# hall_sensors.net
KiCad netlist of a schematic drawn in Altium Designer
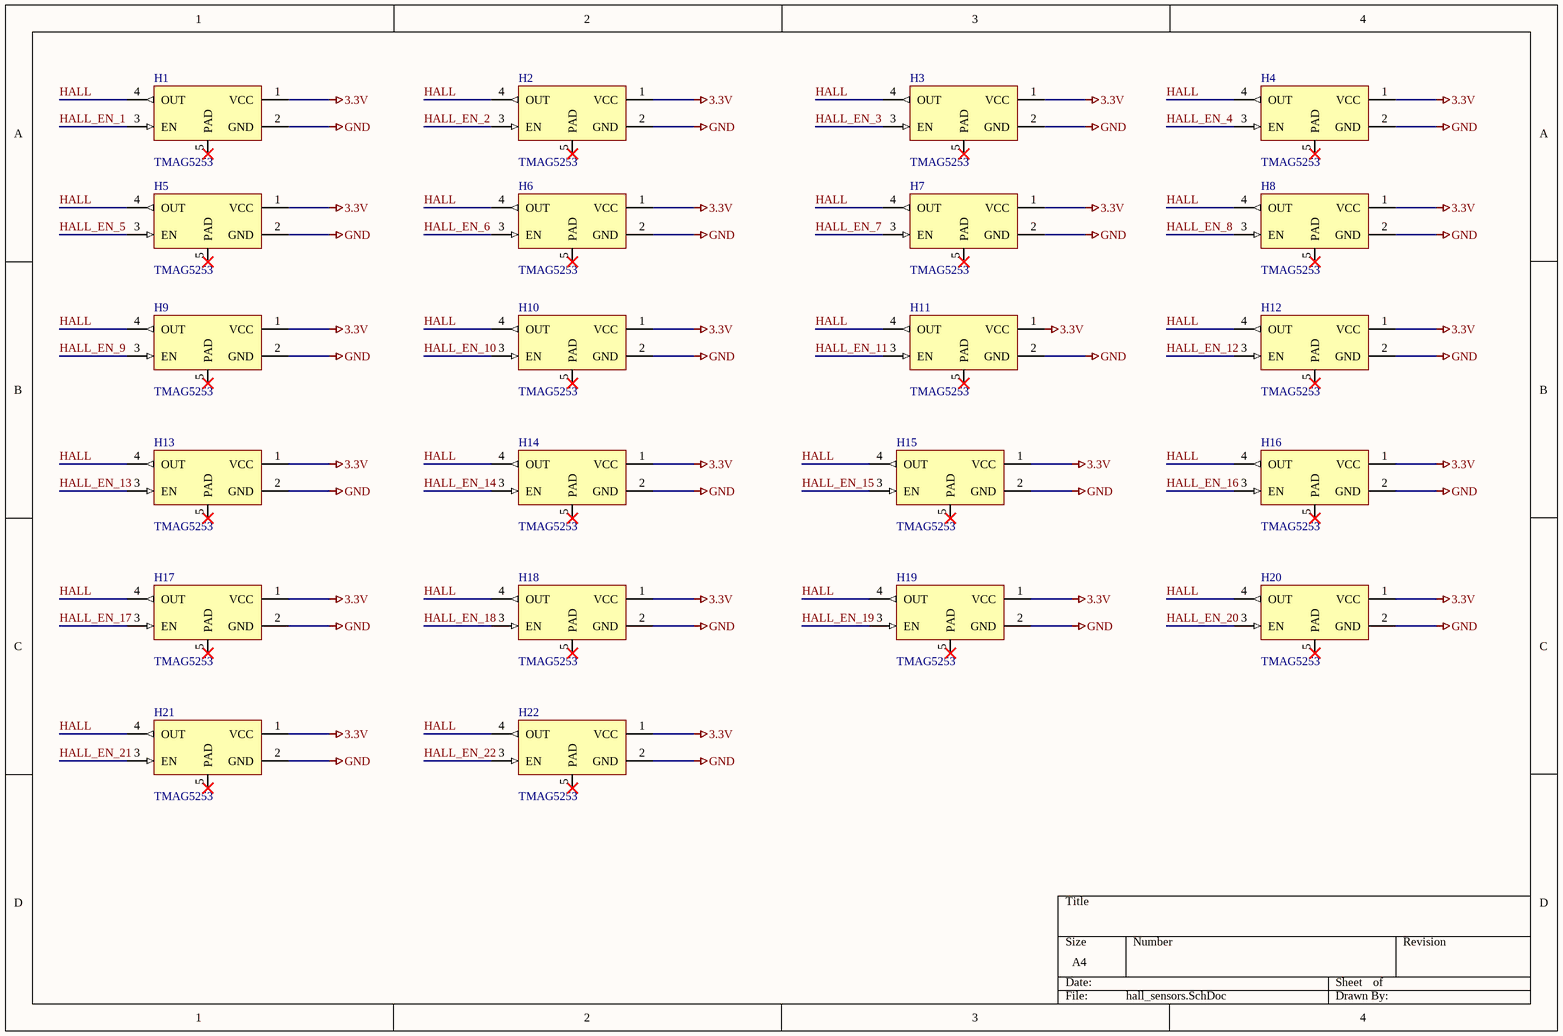
[diagram p0: hall_sensors.SchDoc]

(export (version "E")
  (design (tool "Eeschema 10.0.6"))
  (components
    (comp (ref "H1")
      (value "TMAG5253")
      (footprint "CHOCO_KEYBOARD:IC_TMAG5253BA3IQDMRR")
      (description "Low-power linear Hall-effect sensor with enable pin in ultrasmall X2SON package")
      (fields (field (name "MF") "Texas Instruments") (field (name "MP") "TMAG5253BA3IQDMRR"))
      (libsource (lib "CHOCO_KEYBOARD") (part "TMAG5253"))
    )
    (comp (ref "H2")
      (value "TMAG5253")
      (footprint "CHOCO_KEYBOARD:IC_TMAG5253BA3IQDMRR")
      (description "Low-power linear Hall-effect sensor with enable pin in ultrasmall X2SON package")
      (fields (field (name "MF") "Texas Instruments") (field (name "MP") "TMAG5253BA3IQDMRR"))
      (libsource (lib "CHOCO_KEYBOARD") (part "TMAG5253"))
    )
    (comp (ref "H3")
      (value "TMAG5253")
      (footprint "CHOCO_KEYBOARD:IC_TMAG5253BA3IQDMRR")
      (description "Low-power linear Hall-effect sensor with enable pin in ultrasmall X2SON package")
      (fields (field (name "MF") "Texas Instruments") (field (name "MP") "TMAG5253BA3IQDMRR"))
      (libsource (lib "CHOCO_KEYBOARD") (part "TMAG5253"))
    )
    (comp (ref "H4")
      (value "TMAG5253")
      (footprint "CHOCO_KEYBOARD:IC_TMAG5253BA3IQDMRR")
      (description "Low-power linear Hall-effect sensor with enable pin in ultrasmall X2SON package")
      (fields (field (name "MF") "Texas Instruments") (field (name "MP") "TMAG5253BA3IQDMRR"))
      (libsource (lib "CHOCO_KEYBOARD") (part "TMAG5253"))
    )
    (comp (ref "H5")
      (value "TMAG5253")
      (footprint "CHOCO_KEYBOARD:IC_TMAG5253BA3IQDMRR")
      (description "Low-power linear Hall-effect sensor with enable pin in ultrasmall X2SON package")
      (fields (field (name "MF") "Texas Instruments") (field (name "MP") "TMAG5253BA3IQDMRR"))
      (libsource (lib "CHOCO_KEYBOARD") (part "TMAG5253"))
    )
    (comp (ref "H6")
      (value "TMAG5253")
      (footprint "CHOCO_KEYBOARD:IC_TMAG5253BA3IQDMRR")
      (description "Low-power linear Hall-effect sensor with enable pin in ultrasmall X2SON package")
      (fields (field (name "MF") "Texas Instruments") (field (name "MP") "TMAG5253BA3IQDMRR"))
      (libsource (lib "CHOCO_KEYBOARD") (part "TMAG5253"))
    )
    (comp (ref "H7")
      (value "TMAG5253")
      (footprint "CHOCO_KEYBOARD:IC_TMAG5253BA3IQDMRR")
      (description "Low-power linear Hall-effect sensor with enable pin in ultrasmall X2SON package")
      (fields (field (name "MF") "Texas Instruments") (field (name "MP") "TMAG5253BA3IQDMRR"))
      (libsource (lib "CHOCO_KEYBOARD") (part "TMAG5253"))
    )
    (comp (ref "H8")
      (value "TMAG5253")
      (footprint "CHOCO_KEYBOARD:IC_TMAG5253BA3IQDMRR")
      (description "Low-power linear Hall-effect sensor with enable pin in ultrasmall X2SON package")
      (fields (field (name "MF") "Texas Instruments") (field (name "MP") "TMAG5253BA3IQDMRR"))
      (libsource (lib "CHOCO_KEYBOARD") (part "TMAG5253"))
    )
    (comp (ref "H9")
      (value "TMAG5253")
      (footprint "CHOCO_KEYBOARD:IC_TMAG5253BA3IQDMRR")
      (description "Low-power linear Hall-effect sensor with enable pin in ultrasmall X2SON package")
      (fields (field (name "MF") "Texas Instruments") (field (name "MP") "TMAG5253BA3IQDMRR"))
      (libsource (lib "CHOCO_KEYBOARD") (part "TMAG5253"))
    )
    (comp (ref "H10")
      (value "TMAG5253")
      (footprint "CHOCO_KEYBOARD:IC_TMAG5253BA3IQDMRR")
      (description "Low-power linear Hall-effect sensor with enable pin in ultrasmall X2SON package")
      (fields (field (name "MF") "Texas Instruments") (field (name "MP") "TMAG5253BA3IQDMRR"))
      (libsource (lib "CHOCO_KEYBOARD") (part "TMAG5253"))
    )
    (comp (ref "H11")
      (value "TMAG5253")
      (footprint "CHOCO_KEYBOARD:IC_TMAG5253BA3IQDMRR")
      (description "Low-power linear Hall-effect sensor with enable pin in ultrasmall X2SON package")
      (fields (field (name "MF") "Texas Instruments") (field (name "MP") "TMAG5253BA3IQDMRR"))
      (libsource (lib "CHOCO_KEYBOARD") (part "TMAG5253"))
    )
    (comp (ref "H12")
      (value "TMAG5253")
      (footprint "CHOCO_KEYBOARD:IC_TMAG5253BA3IQDMRR")
      (description "Low-power linear Hall-effect sensor with enable pin in ultrasmall X2SON package")
      (fields (field (name "MF") "Texas Instruments") (field (name "MP") "TMAG5253BA3IQDMRR"))
      (libsource (lib "CHOCO_KEYBOARD") (part "TMAG5253"))
    )
    (comp (ref "H13")
      (value "TMAG5253")
      (footprint "CHOCO_KEYBOARD:IC_TMAG5253BA3IQDMRR")
      (description "Low-power linear Hall-effect sensor with enable pin in ultrasmall X2SON package")
      (fields (field (name "MF") "Texas Instruments") (field (name "MP") "TMAG5253BA3IQDMRR"))
      (libsource (lib "CHOCO_KEYBOARD") (part "TMAG5253"))
    )
    (comp (ref "H14")
      (value "TMAG5253")
      (footprint "CHOCO_KEYBOARD:IC_TMAG5253BA3IQDMRR")
      (description "Low-power linear Hall-effect sensor with enable pin in ultrasmall X2SON package")
      (fields (field (name "MF") "Texas Instruments") (field (name "MP") "TMAG5253BA3IQDMRR"))
      (libsource (lib "CHOCO_KEYBOARD") (part "TMAG5253"))
    )
    (comp (ref "H15")
      (value "TMAG5253")
      (footprint "CHOCO_KEYBOARD:IC_TMAG5253BA3IQDMRR")
      (description "Low-power linear Hall-effect sensor with enable pin in ultrasmall X2SON package")
      (fields (field (name "MF") "Texas Instruments") (field (name "MP") "TMAG5253BA3IQDMRR"))
      (libsource (lib "CHOCO_KEYBOARD") (part "TMAG5253"))
    )
    (comp (ref "H16")
      (value "TMAG5253")
      (footprint "CHOCO_KEYBOARD:IC_TMAG5253BA3IQDMRR")
      (description "Low-power linear Hall-effect sensor with enable pin in ultrasmall X2SON package")
      (fields (field (name "MF") "Texas Instruments") (field (name "MP") "TMAG5253BA3IQDMRR"))
      (libsource (lib "CHOCO_KEYBOARD") (part "TMAG5253"))
    )
    (comp (ref "H17")
      (value "TMAG5253")
      (footprint "CHOCO_KEYBOARD:IC_TMAG5253BA3IQDMRR")
      (description "Low-power linear Hall-effect sensor with enable pin in ultrasmall X2SON package")
      (fields (field (name "MF") "Texas Instruments") (field (name "MP") "TMAG5253BA3IQDMRR"))
      (libsource (lib "CHOCO_KEYBOARD") (part "TMAG5253"))
    )
    (comp (ref "H18")
      (value "TMAG5253")
      (footprint "CHOCO_KEYBOARD:IC_TMAG5253BA3IQDMRR")
      (description "Low-power linear Hall-effect sensor with enable pin in ultrasmall X2SON package")
      (fields (field (name "MF") "Texas Instruments") (field (name "MP") "TMAG5253BA3IQDMRR"))
      (libsource (lib "CHOCO_KEYBOARD") (part "TMAG5253"))
    )
    (comp (ref "H19")
      (value "TMAG5253")
      (footprint "CHOCO_KEYBOARD:IC_TMAG5253BA3IQDMRR")
      (description "Low-power linear Hall-effect sensor with enable pin in ultrasmall X2SON package")
      (fields (field (name "MF") "Texas Instruments") (field (name "MP") "TMAG5253BA3IQDMRR"))
      (libsource (lib "CHOCO_KEYBOARD") (part "TMAG5253"))
    )
    (comp (ref "H20")
      (value "TMAG5253")
      (footprint "CHOCO_KEYBOARD:IC_TMAG5253BA3IQDMRR")
      (description "Low-power linear Hall-effect sensor with enable pin in ultrasmall X2SON package")
      (fields (field (name "MF") "Texas Instruments") (field (name "MP") "TMAG5253BA3IQDMRR"))
      (libsource (lib "CHOCO_KEYBOARD") (part "TMAG5253"))
    )
    (comp (ref "H21")
      (value "TMAG5253")
      (footprint "CHOCO_KEYBOARD:IC_TMAG5253BA3IQDMRR")
      (description "Low-power linear Hall-effect sensor with enable pin in ultrasmall X2SON package")
      (fields (field (name "MF") "Texas Instruments") (field (name "MP") "TMAG5253BA3IQDMRR"))
      (libsource (lib "CHOCO_KEYBOARD") (part "TMAG5253"))
    )
    (comp (ref "H22")
      (value "TMAG5253")
      (footprint "CHOCO_KEYBOARD:IC_TMAG5253BA3IQDMRR")
      (description "Low-power linear Hall-effect sensor with enable pin in ultrasmall X2SON package")
      (fields (field (name "MF") "Texas Instruments") (field (name "MP") "TMAG5253BA3IQDMRR"))
      (libsource (lib "CHOCO_KEYBOARD") (part "TMAG5253"))
    )
  )
  (nets
    (net (code "1") (name "/HALL") (class "Default")
      (node (ref "H1") (pin "4") (pinfunction "OUT_4") (pintype "output"))
      (node (ref "H10") (pin "4") (pinfunction "OUT_4") (pintype "output"))
      (node (ref "H11") (pin "4") (pinfunction "OUT_4") (pintype "output"))
      (node (ref "H12") (pin "4") (pinfunction "OUT_4") (pintype "output"))
      (node (ref "H13") (pin "4") (pinfunction "OUT_4") (pintype "output"))
      (node (ref "H14") (pin "4") (pinfunction "OUT_4") (pintype "output"))
      (node (ref "H15") (pin "4") (pinfunction "OUT_4") (pintype "output"))
      (node (ref "H16") (pin "4") (pinfunction "OUT_4") (pintype "output"))
      (node (ref "H17") (pin "4") (pinfunction "OUT_4") (pintype "output"))
      (node (ref "H18") (pin "4") (pinfunction "OUT_4") (pintype "output"))
      (node (ref "H19") (pin "4") (pinfunction "OUT_4") (pintype "output"))
      (node (ref "H2") (pin "4") (pinfunction "OUT_4") (pintype "output"))
      (node (ref "H20") (pin "4") (pinfunction "OUT_4") (pintype "output"))
      (node (ref "H21") (pin "4") (pinfunction "OUT_4") (pintype "output"))
      (node (ref "H22") (pin "4") (pinfunction "OUT_4") (pintype "output"))
      (node (ref "H3") (pin "4") (pinfunction "OUT_4") (pintype "output"))
      (node (ref "H4") (pin "4") (pinfunction "OUT_4") (pintype "output"))
      (node (ref "H5") (pin "4") (pinfunction "OUT_4") (pintype "output"))
      (node (ref "H6") (pin "4") (pinfunction "OUT_4") (pintype "output"))
      (node (ref "H7") (pin "4") (pinfunction "OUT_4") (pintype "output"))
      (node (ref "H8") (pin "4") (pinfunction "OUT_4") (pintype "output"))
      (node (ref "H9") (pin "4") (pinfunction "OUT_4") (pintype "output"))
    )
    (net (code "2") (name "/HALL_EN_1") (class "Default")
      (node (ref "H1") (pin "3") (pinfunction "EN_3") (pintype "input"))
    )
    (net (code "3") (name "/HALL_EN_2") (class "Default")
      (node (ref "H2") (pin "3") (pinfunction "EN_3") (pintype "input"))
    )
    (net (code "4") (name "/HALL_EN_3") (class "Default")
      (node (ref "H3") (pin "3") (pinfunction "EN_3") (pintype "input"))
    )
    (net (code "5") (name "/HALL_EN_4") (class "Default")
      (node (ref "H4") (pin "3") (pinfunction "EN_3") (pintype "input"))
    )
    (net (code "6") (name "/HALL_EN_5") (class "Default")
      (node (ref "H5") (pin "3") (pinfunction "EN_3") (pintype "input"))
    )
    (net (code "7") (name "/HALL_EN_6") (class "Default")
      (node (ref "H6") (pin "3") (pinfunction "EN_3") (pintype "input"))
    )
    (net (code "8") (name "/HALL_EN_7") (class "Default")
      (node (ref "H7") (pin "3") (pinfunction "EN_3") (pintype "input"))
    )
    (net (code "9") (name "/HALL_EN_8") (class "Default")
      (node (ref "H8") (pin "3") (pinfunction "EN_3") (pintype "input"))
    )
    (net (code "10") (name "/HALL_EN_9") (class "Default")
      (node (ref "H9") (pin "3") (pinfunction "EN_3") (pintype "input"))
    )
    (net (code "11") (name "/HALL_EN_10") (class "Default")
      (node (ref "H10") (pin "3") (pinfunction "EN_3") (pintype "input"))
    )
    (net (code "12") (name "/HALL_EN_11") (class "Default")
      (node (ref "H11") (pin "3") (pinfunction "EN_3") (pintype "input"))
    )
    (net (code "13") (name "/HALL_EN_12") (class "Default")
      (node (ref "H12") (pin "3") (pinfunction "EN_3") (pintype "input"))
    )
    (net (code "14") (name "/HALL_EN_13") (class "Default")
      (node (ref "H13") (pin "3") (pinfunction "EN_3") (pintype "input"))
    )
    (net (code "15") (name "/HALL_EN_14") (class "Default")
      (node (ref "H14") (pin "3") (pinfunction "EN_3") (pintype "input"))
    )
    (net (code "16") (name "/HALL_EN_15") (class "Default")
      (node (ref "H15") (pin "3") (pinfunction "EN_3") (pintype "input"))
    )
    (net (code "17") (name "/HALL_EN_16") (class "Default")
      (node (ref "H16") (pin "3") (pinfunction "EN_3") (pintype "input"))
    )
    (net (code "18") (name "/HALL_EN_17") (class "Default")
      (node (ref "H17") (pin "3") (pinfunction "EN_3") (pintype "input"))
    )
    (net (code "19") (name "/HALL_EN_18") (class "Default")
      (node (ref "H18") (pin "3") (pinfunction "EN_3") (pintype "input"))
    )
    (net (code "20") (name "/HALL_EN_19") (class "Default")
      (node (ref "H19") (pin "3") (pinfunction "EN_3") (pintype "input"))
    )
    (net (code "21") (name "/HALL_EN_20") (class "Default")
      (node (ref "H20") (pin "3") (pinfunction "EN_3") (pintype "input"))
    )
    (net (code "22") (name "/HALL_EN_21") (class "Default")
      (node (ref "H21") (pin "3") (pinfunction "EN_3") (pintype "input"))
    )
    (net (code "23") (name "/HALL_EN_22") (class "Default")
      (node (ref "H22") (pin "3") (pinfunction "EN_3") (pintype "input"))
    )
    (net (code "24") (name "3.3V") (class "Default")
      (node (ref "H1") (pin "1") (pinfunction "VCC_1") (pintype "power_in"))
      (node (ref "H10") (pin "1") (pinfunction "VCC_1") (pintype "power_in"))
      (node (ref "H11") (pin "1") (pinfunction "VCC_1") (pintype "power_in"))
      (node (ref "H12") (pin "1") (pinfunction "VCC_1") (pintype "power_in"))
      (node (ref "H13") (pin "1") (pinfunction "VCC_1") (pintype "power_in"))
      (node (ref "H14") (pin "1") (pinfunction "VCC_1") (pintype "power_in"))
      (node (ref "H15") (pin "1") (pinfunction "VCC_1") (pintype "power_in"))
      (node (ref "H16") (pin "1") (pinfunction "VCC_1") (pintype "power_in"))
      (node (ref "H17") (pin "1") (pinfunction "VCC_1") (pintype "power_in"))
      (node (ref "H18") (pin "1") (pinfunction "VCC_1") (pintype "power_in"))
      (node (ref "H19") (pin "1") (pinfunction "VCC_1") (pintype "power_in"))
      (node (ref "H2") (pin "1") (pinfunction "VCC_1") (pintype "power_in"))
      (node (ref "H20") (pin "1") (pinfunction "VCC_1") (pintype "power_in"))
      (node (ref "H21") (pin "1") (pinfunction "VCC_1") (pintype "power_in"))
      (node (ref "H22") (pin "1") (pinfunction "VCC_1") (pintype "power_in"))
      (node (ref "H3") (pin "1") (pinfunction "VCC_1") (pintype "power_in"))
      (node (ref "H4") (pin "1") (pinfunction "VCC_1") (pintype "power_in"))
      (node (ref "H5") (pin "1") (pinfunction "VCC_1") (pintype "power_in"))
      (node (ref "H6") (pin "1") (pinfunction "VCC_1") (pintype "power_in"))
      (node (ref "H7") (pin "1") (pinfunction "VCC_1") (pintype "power_in"))
      (node (ref "H8") (pin "1") (pinfunction "VCC_1") (pintype "power_in"))
      (node (ref "H9") (pin "1") (pinfunction "VCC_1") (pintype "power_in"))
    )
    (net (code "25") (name "GND") (class "Default")
      (node (ref "H1") (pin "2") (pinfunction "GND_2") (pintype "power_in"))
      (node (ref "H10") (pin "2") (pinfunction "GND_2") (pintype "power_in"))
      (node (ref "H11") (pin "2") (pinfunction "GND_2") (pintype "power_in"))
      (node (ref "H12") (pin "2") (pinfunction "GND_2") (pintype "power_in"))
      (node (ref "H13") (pin "2") (pinfunction "GND_2") (pintype "power_in"))
      (node (ref "H14") (pin "2") (pinfunction "GND_2") (pintype "power_in"))
      (node (ref "H15") (pin "2") (pinfunction "GND_2") (pintype "power_in"))
      (node (ref "H16") (pin "2") (pinfunction "GND_2") (pintype "power_in"))
      (node (ref "H17") (pin "2") (pinfunction "GND_2") (pintype "power_in"))
      (node (ref "H18") (pin "2") (pinfunction "GND_2") (pintype "power_in"))
      (node (ref "H19") (pin "2") (pinfunction "GND_2") (pintype "power_in"))
      (node (ref "H2") (pin "2") (pinfunction "GND_2") (pintype "power_in"))
      (node (ref "H20") (pin "2") (pinfunction "GND_2") (pintype "power_in"))
      (node (ref "H21") (pin "2") (pinfunction "GND_2") (pintype "power_in"))
      (node (ref "H22") (pin "2") (pinfunction "GND_2") (pintype "power_in"))
      (node (ref "H3") (pin "2") (pinfunction "GND_2") (pintype "power_in"))
      (node (ref "H4") (pin "2") (pinfunction "GND_2") (pintype "power_in"))
      (node (ref "H5") (pin "2") (pinfunction "GND_2") (pintype "power_in"))
      (node (ref "H6") (pin "2") (pinfunction "GND_2") (pintype "power_in"))
      (node (ref "H7") (pin "2") (pinfunction "GND_2") (pintype "power_in"))
      (node (ref "H8") (pin "2") (pinfunction "GND_2") (pintype "power_in"))
      (node (ref "H9") (pin "2") (pinfunction "GND_2") (pintype "power_in"))
    )
    (net (code "26") (name "unconnected-(H1-PAD-Pad5)") (class "Default")
      (node (ref "H1") (pin "5") (pinfunction "PAD_5") (pintype "passive+no_connect"))
    )
    (net (code "27") (name "unconnected-(H2-PAD-Pad5)") (class "Default")
      (node (ref "H2") (pin "5") (pinfunction "PAD_5") (pintype "passive+no_connect"))
    )
    (net (code "28") (name "unconnected-(H3-PAD-Pad5)") (class "Default")
      (node (ref "H3") (pin "5") (pinfunction "PAD_5") (pintype "passive+no_connect"))
    )
    (net (code "29") (name "unconnected-(H4-PAD-Pad5)") (class "Default")
      (node (ref "H4") (pin "5") (pinfunction "PAD_5") (pintype "passive+no_connect"))
    )
    (net (code "30") (name "unconnected-(H5-PAD-Pad5)") (class "Default")
      (node (ref "H5") (pin "5") (pinfunction "PAD_5") (pintype "passive+no_connect"))
    )
    (net (code "31") (name "unconnected-(H6-PAD-Pad5)") (class "Default")
      (node (ref "H6") (pin "5") (pinfunction "PAD_5") (pintype "passive+no_connect"))
    )
    (net (code "32") (name "unconnected-(H7-PAD-Pad5)") (class "Default")
      (node (ref "H7") (pin "5") (pinfunction "PAD_5") (pintype "passive+no_connect"))
    )
    (net (code "33") (name "unconnected-(H8-PAD-Pad5)") (class "Default")
      (node (ref "H8") (pin "5") (pinfunction "PAD_5") (pintype "passive+no_connect"))
    )
    (net (code "34") (name "unconnected-(H9-PAD-Pad5)") (class "Default")
      (node (ref "H9") (pin "5") (pinfunction "PAD_5") (pintype "passive+no_connect"))
    )
    (net (code "35") (name "unconnected-(H10-PAD-Pad5)") (class "Default")
      (node (ref "H10") (pin "5") (pinfunction "PAD_5") (pintype "passive+no_connect"))
    )
    (net (code "36") (name "unconnected-(H11-PAD-Pad5)") (class "Default")
      (node (ref "H11") (pin "5") (pinfunction "PAD_5") (pintype "passive+no_connect"))
    )
    (net (code "37") (name "unconnected-(H12-PAD-Pad5)") (class "Default")
      (node (ref "H12") (pin "5") (pinfunction "PAD_5") (pintype "passive+no_connect"))
    )
    (net (code "38") (name "unconnected-(H13-PAD-Pad5)") (class "Default")
      (node (ref "H13") (pin "5") (pinfunction "PAD_5") (pintype "passive+no_connect"))
    )
    (net (code "39") (name "unconnected-(H14-PAD-Pad5)") (class "Default")
      (node (ref "H14") (pin "5") (pinfunction "PAD_5") (pintype "passive+no_connect"))
    )
    (net (code "40") (name "unconnected-(H15-PAD-Pad5)") (class "Default")
      (node (ref "H15") (pin "5") (pinfunction "PAD_5") (pintype "passive+no_connect"))
    )
    (net (code "41") (name "unconnected-(H16-PAD-Pad5)") (class "Default")
      (node (ref "H16") (pin "5") (pinfunction "PAD_5") (pintype "passive+no_connect"))
    )
    (net (code "42") (name "unconnected-(H17-PAD-Pad5)") (class "Default")
      (node (ref "H17") (pin "5") (pinfunction "PAD_5") (pintype "passive+no_connect"))
    )
    (net (code "43") (name "unconnected-(H18-PAD-Pad5)") (class "Default")
      (node (ref "H18") (pin "5") (pinfunction "PAD_5") (pintype "passive+no_connect"))
    )
    (net (code "44") (name "unconnected-(H19-PAD-Pad5)") (class "Default")
      (node (ref "H19") (pin "5") (pinfunction "PAD_5") (pintype "passive+no_connect"))
    )
    (net (code "45") (name "unconnected-(H20-PAD-Pad5)") (class "Default")
      (node (ref "H20") (pin "5") (pinfunction "PAD_5") (pintype "passive+no_connect"))
    )
    (net (code "46") (name "unconnected-(H21-PAD-Pad5)") (class "Default")
      (node (ref "H21") (pin "5") (pinfunction "PAD_5") (pintype "passive+no_connect"))
    )
    (net (code "47") (name "unconnected-(H22-PAD-Pad5)") (class "Default")
      (node (ref "H22") (pin "5") (pinfunction "PAD_5") (pintype "passive+no_connect"))
    )
  )
)
